# rect.net
KiCad netlist of a schematic drawn in Altium Designer
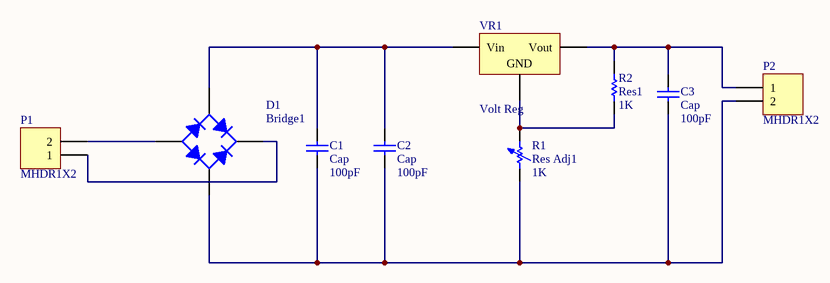
[diagram p0: rect.SchDoc]

(export (version "E")
  (design (tool "Eeschema 10.0.6"))
  (components
    (comp (ref "C1")
      (value "Cap")
      (footprint "RAD-0.3")
      (description "Capacitor")
      (fields (field (name "ALTIUM_VALUE") "100pF") (field (name "PUBLISHER") "Altium Limited"))
      (libsource (lib "Miscellaneous Devices") (part "Cap"))
    )
    (comp (ref "C2")
      (value "Cap")
      (footprint "RAD-0.3")
      (description "Capacitor")
      (fields (field (name "ALTIUM_VALUE") "100pF") (field (name "PUBLISHER") "Altium Limited"))
      (libsource (lib "Miscellaneous Devices") (part "Cap"))
    )
    (comp (ref "C3")
      (value "Cap")
      (footprint "RAD-0.3")
      (description "Capacitor")
      (fields (field (name "ALTIUM_VALUE") "100pF") (field (name "PUBLISHER") "Altium Limited"))
      (libsource (lib "Miscellaneous Devices") (part "Cap"))
    )
    (comp (ref "D1")
      (value "Bridge1")
      (footprint "D-38")
      (description "Full Wave Diode Bridge")
      (fields (field (name "PUBLISHER") "Altium Limited"))
      (libsource (lib "Miscellaneous Devices") (part "Bridge1"))
    )
    (comp (ref "P1")
      (value "MHDR1X2")
      (footprint "MHDR1X2")
      (description "Header, 2-Pin")
      (fields (field (name "PUBLISHER") "Altium Limited"))
      (libsource (lib "") (part "MHDR1X2_1"))
    )
    (comp (ref "P2")
      (value "MHDR1X2")
      (footprint "MHDR1X2")
      (description "Header, 2-Pin")
      (fields (field (name "PUBLISHER") "Altium Limited"))
      (libsource (lib "Miscellaneous Connectors") (part "MHDR1X2"))
    )
    (comp (ref "R1")
      (value "Res Adj1")
      (footprint "AXIAL-0.7")
      (description "Variable Resistor")
      (fields (field (name "ALTIUM_VALUE") "1K") (field (name "PUBLISHER") "Altium Limited"))
      (libsource (lib "Miscellaneous Devices") (part "Res Adj1"))
    )
    (comp (ref "R2")
      (value "Res1")
      (footprint "AXIAL-0.3")
      (description "Resistor")
      (fields (field (name "ALTIUM_VALUE") "1K") (field (name "PUBLISHER") "Altium Limited"))
      (libsource (lib "Miscellaneous Devices") (part "Res1"))
    )
    (comp (ref "VR1")
      (value "Volt Reg")
      (footprint "D2PAK_N")
      (description "Voltage Regulator")
      (fields (field (name "PUBLISHER") "Altium Limited"))
      (libsource (lib "Miscellaneous Devices") (part "Volt Reg"))
    )
  )
  (nets
    (net (code "1") (name "Net-(C1-Pad1)") (class "Default")
      (node (ref "C1") (pin "1") (pinfunction "1_1") (pintype "passive"))
      (node (ref "C2") (pin "1") (pinfunction "1_1") (pintype "passive"))
      (node (ref "C3") (pin "1") (pinfunction "1_1") (pintype "passive"))
      (node (ref "D1") (pin "2") (pinfunction "C_2") (pintype "passive"))
      (node (ref "P2") (pin "2") (pinfunction "2_2") (pintype "passive"))
      (node (ref "R1") (pin "1") (pinfunction "1_1") (pintype "passive"))
    )
    (net (code "2") (name "Net-(D1-A)") (class "Default")
      (node (ref "D1") (pin "3") (pinfunction "A_3") (pintype "passive"))
      (node (ref "P1") (pin "2") (pinfunction "2_2") (pintype "passive"))
    )
    (net (code "3") (name "Net-(D1-K)") (class "Default")
      (node (ref "D1") (pin "1") (pinfunction "K_1") (pintype "passive"))
      (node (ref "P1") (pin "1") (pinfunction "1_1") (pintype "passive"))
    )
    (net (code "4") (name "Net-(VR1-GND)") (class "Default")
      (node (ref "R1") (pin "2") (pinfunction "2_2") (pintype "passive"))
      (node (ref "R2") (pin "1") (pinfunction "1_1") (pintype "passive"))
      (node (ref "VR1") (pin "2") (pinfunction "GND_2") (pintype "passive"))
    )
    (net (code "5") (name "Net-(VR1-Vin)") (class "Default")
      (node (ref "C1") (pin "2") (pinfunction "2_2") (pintype "passive"))
      (node (ref "C2") (pin "2") (pinfunction "2_2") (pintype "passive"))
      (node (ref "D1") (pin "4") (pinfunction "C_4") (pintype "passive"))
      (node (ref "VR1") (pin "1") (pinfunction "Vin_1") (pintype "passive"))
    )
    (net (code "6") (name "Net-(VR1-Vout)") (class "Default")
      (node (ref "C3") (pin "2") (pinfunction "2_2") (pintype "passive"))
      (node (ref "P2") (pin "1") (pinfunction "1_1") (pintype "passive"))
      (node (ref "R2") (pin "2") (pinfunction "2_2") (pintype "passive"))
      (node (ref "VR1") (pin "3") (pinfunction "Vout_3") (pintype "passive"))
    )
  )
)
